# DT_AZP1524A1_SCH1_SHEET2__00A.net
KiCad netlist of a schematic drawn in Altium Designer
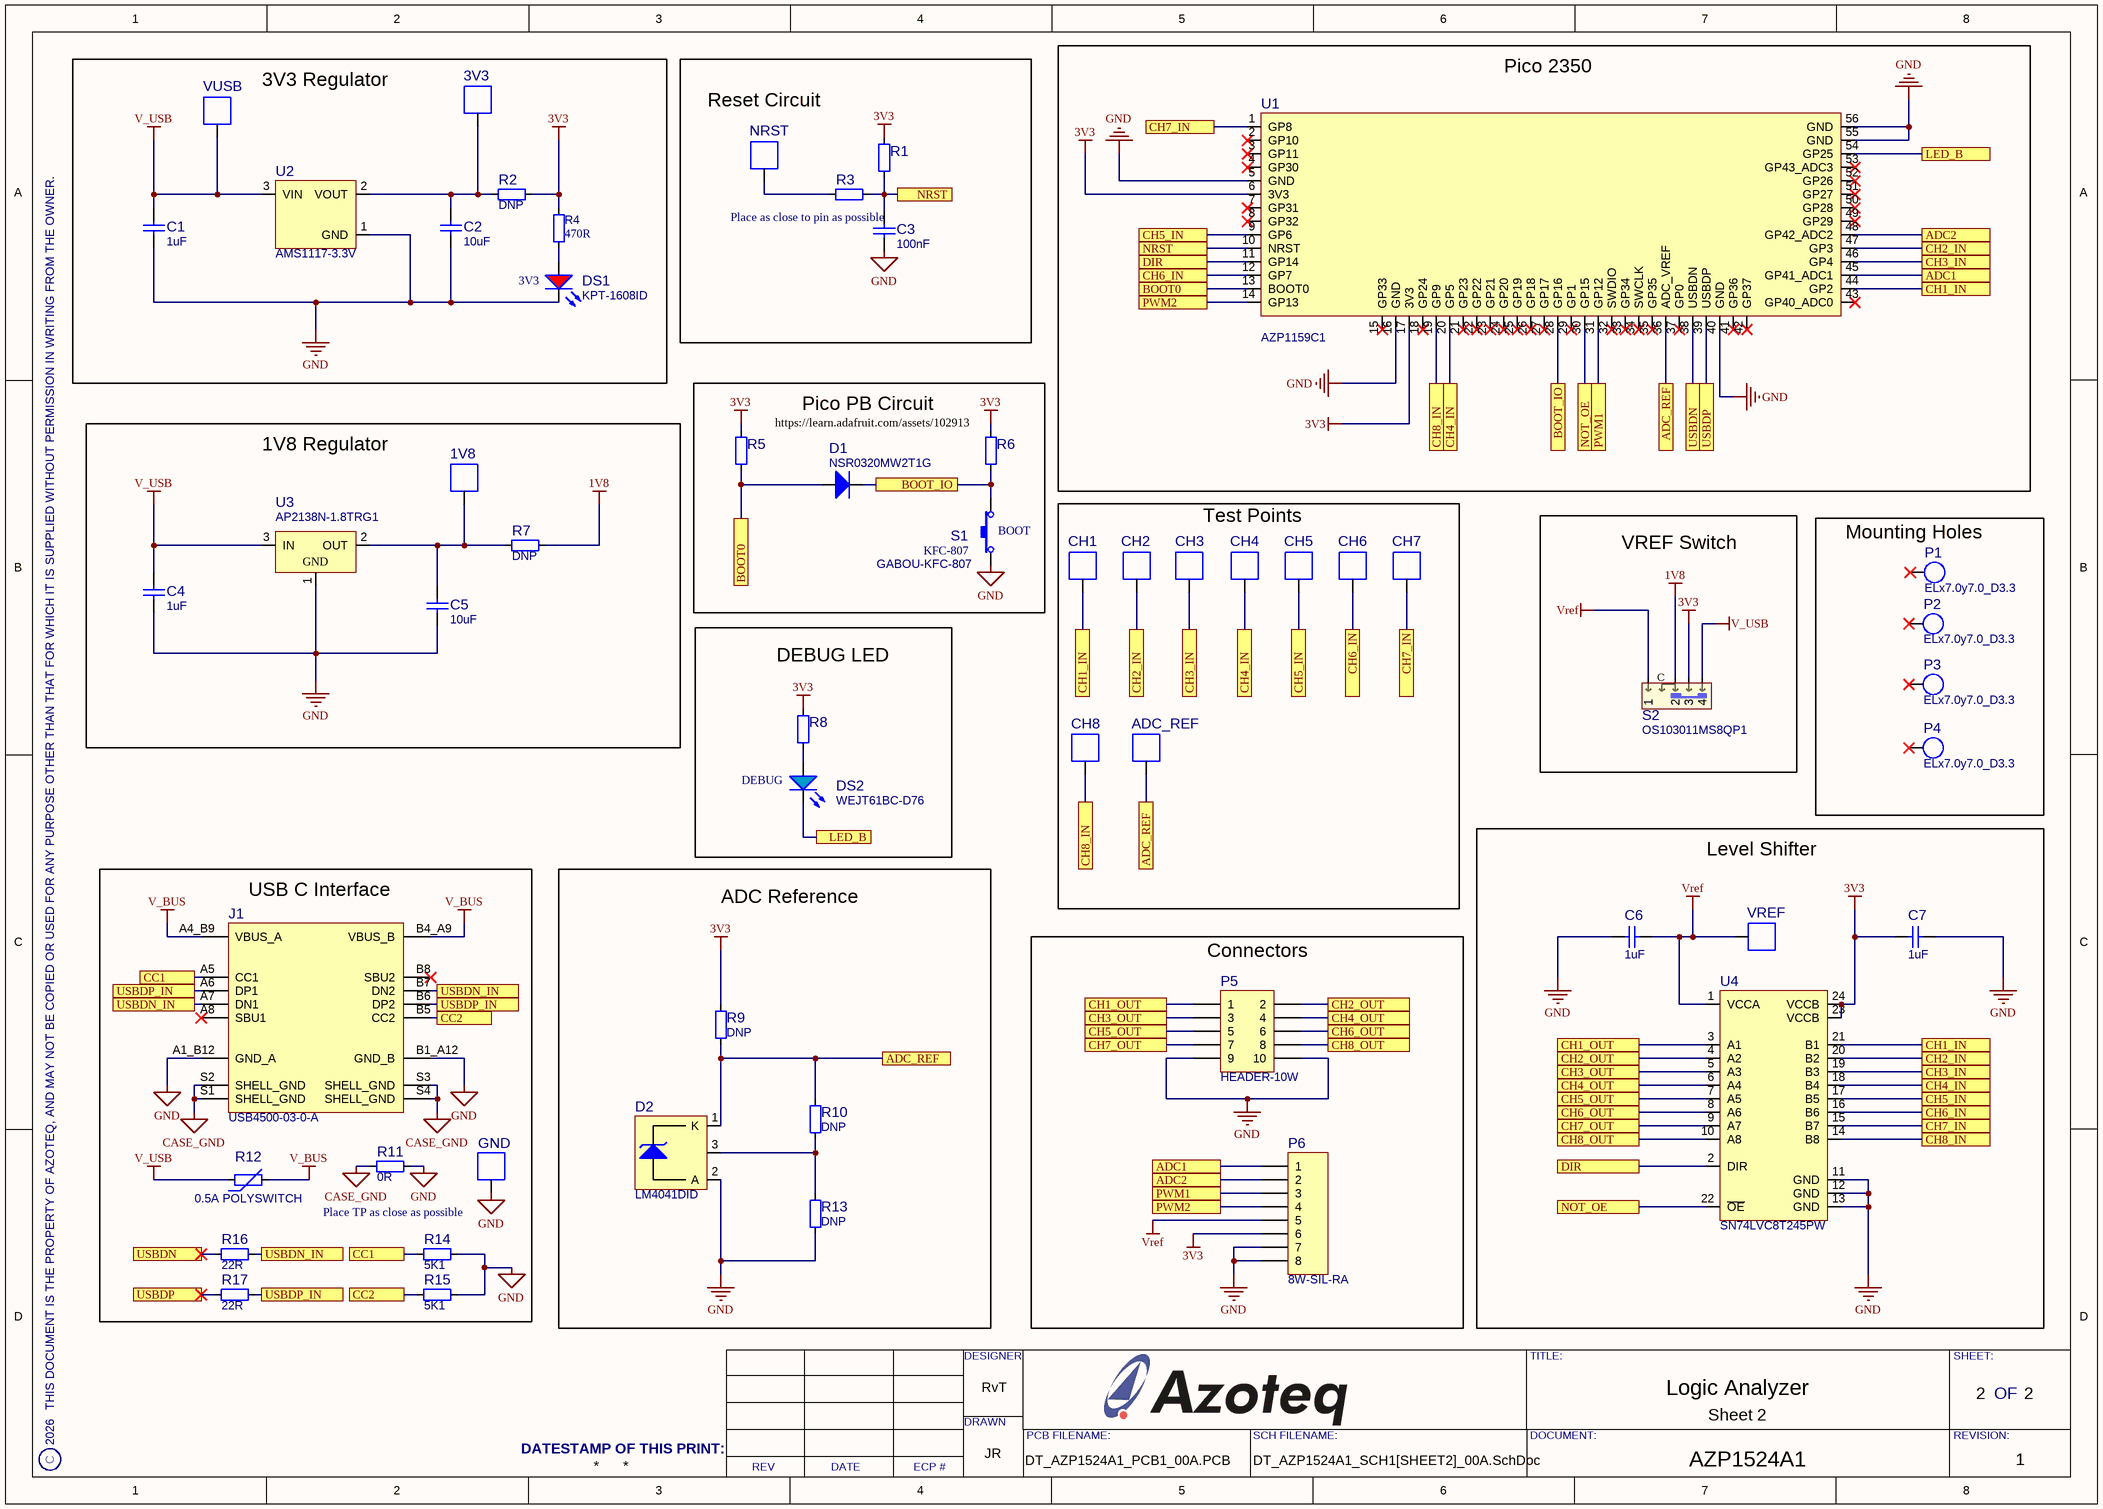
[diagram p0: DT_AZP1524A1_SCH1[SHEET2]_00A.SchDoc]

(export (version "E")
  (design (tool "Eeschema 10.0.6"))
  (components
    (comp (ref "1V8")
      (value "~")
      (footprint "TEST-POINT-1.5MM")
      (fields (field (name "CHECKED_BY") "*"))
      (libsource (lib "Miscellaneous") (part "TEST-POINT-SMD-1.5MM"))
    )
    (comp (ref "3V3")
      (value "~")
      (footprint "TEST-POINT-1.5MM")
      (fields (field (name "CHECKED_BY") "*"))
      (libsource (lib "Miscellaneous") (part "TEST-POINT-SMD-1.5MM"))
    )
    (comp (ref "ADC_REF")
      (value "~")
      (footprint "TEST-POINT-1.5MM")
      (fields (field (name "CHECKED_BY") "*"))
      (libsource (lib "Miscellaneous") (part "TEST-POINT-SMD-1.5MM"))
    )
    (comp (ref "C1")
      (value "1uF")
      (footprint "C-0603")
      (description "Capacitor, Ceramic, 1uF, 0603, X5R, 10%, 10V")
      (fields
        (field (name "INT_PART_NUMBER") "CAP0021")
        (field (name "MANUFACTURER") "Samsung")
        (field (name "CHECKED_BY") "Jason Reinecke")
      )
      (libsource (lib "Passive") (part "CAP 1u0F 0603 CER X5R 10% 10V"))
    )
    (comp (ref "C2")
      (value "10uF")
      (footprint "C-0603")
      (description "Capacitor, Ceramic, 10uF, 0603, X5R, 20%, 6V3 SAMSUNG")
      (fields
        (field (name "INT_PART_NUMBER") "CAP0076")
        (field (name "MANUFACTURER") "SAMSUNG")
        (field (name "CHECKED_BY") "Jason Reinecke")
      )
      (libsource (lib "Passive") (part "CAP 10uF 0603 CER X5R 20% 6V3 SAMSUNG"))
    )
    (comp (ref "C3")
      (value "100nF")
      (footprint "C-0603")
      (description "Capacitor, Ceramic, 100nF, 0603, X7R, 10%, 50V")
      (fields
        (field (name "INT_PART_NUMBER") "CAP0032")
        (field (name "MANUFACTURER") "Samsung")
        (field (name "CHECKED_BY") "Jason Reinecke")
      )
      (libsource (lib "Passive") (part "CAP 100nF 0603 CER X7R 10% 50V"))
    )
    (comp (ref "C4")
      (value "1uF")
      (footprint "C-0603")
      (description "Capacitor, Ceramic, 1uF, 0603, X5R, 10%, 10V")
      (fields
        (field (name "INT_PART_NUMBER") "CAP0021")
        (field (name "MANUFACTURER") "Samsung")
        (field (name "CHECKED_BY") "Jason Reinecke")
      )
      (libsource (lib "Passive") (part "CAP 1u0F 0603 CER X5R 10% 10V"))
    )
    (comp (ref "C5")
      (value "10uF")
      (footprint "C-0603")
      (description "Capacitor, Ceramic, 10uF, 0603, X5R, 20%, 6V3 SAMSUNG")
      (fields
        (field (name "INT_PART_NUMBER") "CAP0076")
        (field (name "MANUFACTURER") "SAMSUNG")
        (field (name "CHECKED_BY") "Jason Reinecke")
      )
      (libsource (lib "Passive") (part "CAP 10uF 0603 CER X5R 20% 6V3 SAMSUNG"))
    )
    (comp (ref "C6")
      (value "1uF")
      (footprint "C-0603")
      (description "Capacitor, Ceramic, 1uF, 0603, X5R, 10%, 10V")
      (fields
        (field (name "INT_PART_NUMBER") "CAP0021")
        (field (name "MANUFACTURER") "Samsung")
        (field (name "CHECKED_BY") "Jason Reinecke")
      )
      (libsource (lib "Passive") (part "CAP 1u0F 0603 CER X5R 10% 10V"))
    )
    (comp (ref "C7")
      (value "1uF")
      (footprint "C-0603")
      (description "Capacitor, Ceramic, 1uF, 0603, X5R, 10%, 10V")
      (fields
        (field (name "INT_PART_NUMBER") "CAP0021")
        (field (name "MANUFACTURER") "Samsung")
        (field (name "CHECKED_BY") "Jason Reinecke")
      )
      (libsource (lib "Passive") (part "CAP 1u0F 0603 CER X5R 10% 10V"))
    )
    (comp (ref "CH1")
      (value "~")
      (footprint "TEST-POINT-1.5MM")
      (fields (field (name "CHECKED_BY") "*"))
      (libsource (lib "Miscellaneous") (part "TEST-POINT-SMD-1.5MM"))
    )
    (comp (ref "CH2")
      (value "~")
      (footprint "TEST-POINT-1.5MM")
      (fields (field (name "CHECKED_BY") "*"))
      (libsource (lib "Miscellaneous") (part "TEST-POINT-SMD-1.5MM"))
    )
    (comp (ref "CH3")
      (value "~")
      (footprint "TEST-POINT-1.5MM")
      (fields (field (name "CHECKED_BY") "*"))
      (libsource (lib "Miscellaneous") (part "TEST-POINT-SMD-1.5MM"))
    )
    (comp (ref "CH4")
      (value "~")
      (footprint "TEST-POINT-1.5MM")
      (fields (field (name "CHECKED_BY") "*"))
      (libsource (lib "Miscellaneous") (part "TEST-POINT-SMD-1.5MM"))
    )
    (comp (ref "CH5")
      (value "~")
      (footprint "TEST-POINT-1.5MM")
      (fields (field (name "CHECKED_BY") "*"))
      (libsource (lib "Miscellaneous") (part "TEST-POINT-SMD-1.5MM"))
    )
    (comp (ref "CH6")
      (value "~")
      (footprint "TEST-POINT-1.5MM")
      (fields (field (name "CHECKED_BY") "*"))
      (libsource (lib "Miscellaneous") (part "TEST-POINT-SMD-1.5MM"))
    )
    (comp (ref "CH7")
      (value "~")
      (footprint "TEST-POINT-1.5MM")
      (fields (field (name "CHECKED_BY") "*"))
      (libsource (lib "Miscellaneous") (part "TEST-POINT-SMD-1.5MM"))
    )
    (comp (ref "CH8")
      (value "~")
      (footprint "TEST-POINT-1.5MM")
      (fields (field (name "CHECKED_BY") "*"))
      (libsource (lib "Miscellaneous") (part "TEST-POINT-SMD-1.5MM"))
    )
    (comp (ref "D1")
      (value "NSR0320MW2T1G")
      (footprint "D-SOD-323")
      (description "Diode Schottky 20V 1A 2-Pin SOD-323 T/R")
      (fields
        (field (name "INT_PART_NUMBER") "DIO0074")
        (field (name "MANUFACTURER") "ONsemiconductors")
        (field (name "CHECKED_BY") "*")
      )
      (libsource (lib "Discrete") (part "Diode Schottky 20V 1A SOD-323"))
    )
    (comp (ref "D2")
      (value "LM4041DID")
      (footprint "SOT-23")
      (fields (field (name "MANUFACTURER") "Texas Instruments") (field (name "CHECKED_BY") "*"))
      (libsource (lib "Discrete") (part "DIODE-ZENER-LM4041-SOT-23"))
    )
    (comp (ref "DS1")
      (value "KPT-1608ID")
      (footprint "D-LED-RED-0603")
      (fields (field (name "MANUFACTURER") "KingBright") (field (name "CHECKED_BY") "*"))
      (libsource (lib "Discrete") (part "LED-KPT1608ID-RED-0603"))
    )
    (comp (ref "DS2")
      (value "WEJT61BC-D76")
      (footprint "D-LED-BLUE-0603 - WEJ updated")
      (description "LED, WEJT61BC-D76, Blue, Vf=3.2V , If=30mA")
      (fields
        (field (name "INT_PART_NUMBER") "LED0098")
        (field (name "MANUFACTURER") "WEJ")
        (field (name "CHECKED_BY") "*")
      )
      (libsource (lib "Discrete") (part "LED-WEJT61BC-D76-BLUE-0603"))
    )
    (comp (ref "GND")
      (value "~")
      (footprint "TEST-POINT-1.5MM")
      (fields (field (name "CHECKED_BY") "*"))
      (libsource (lib "Miscellaneous") (part "TEST-POINT-SMD-1.5MM"))
    )
    (comp (ref "J1")
      (value "USB4500-03-0-A")
      (footprint "J-USB-GCT-USB4500-03-0-A")
      (description "USB-C TYPE REC 16P, 3U\" MID MNT 0.8MM USB2.0")
      (fields
        (field (name "INT_PART_NUMBER") "NONE")
        (field (name "MANUFACTURER") "GCT")
        (field (name "CHECKED_BY") "Jason Reinecke")
      )
      (libsource (lib "Connectors") (part "USB-GCT-USB4500-03-0-A"))
    )
    (comp (ref "NRST")
      (value "~")
      (footprint "TEST-POINT-1.5MM")
      (fields (field (name "CHECKED_BY") "*"))
      (libsource (lib "Miscellaneous") (part "TEST-POINT-SMD-1.5MM"))
    )
    (comp (ref "P1")
      (value "ELx7.0y7.0_D3.3")
      (footprint "MPAD-X7.0Y7.0_D3.3")
      (fields (field (name "CHECKED_BY") "*"))
      (libsource (lib "MPads") (part "MPAD-ELx7.0y7.0_D3.3"))
    )
    (comp (ref "P2")
      (value "ELx7.0y7.0_D3.3")
      (footprint "MPAD-X7.0Y7.0_D3.3")
      (fields (field (name "CHECKED_BY") "*"))
      (libsource (lib "MPads") (part "MPAD-ELx7.0y7.0_D3.3"))
    )
    (comp (ref "P3")
      (value "ELx7.0y7.0_D3.3")
      (footprint "MPAD-X7.0Y7.0_D3.3")
      (fields (field (name "CHECKED_BY") "*"))
      (libsource (lib "MPads") (part "MPAD-ELx7.0y7.0_D3.3"))
    )
    (comp (ref "P4")
      (value "ELx7.0y7.0_D3.3")
      (footprint "MPAD-X7.0Y7.0_D3.3")
      (fields (field (name "CHECKED_BY") "*"))
      (libsource (lib "MPads") (part "MPAD-ELx7.0y7.0_D3.3"))
    )
    (comp (ref "P5")
      (value "HEADER-10W")
      (footprint "P-BERG-10W-HDR-EDGE")
      (description "Connector, Header, Edge Mount,DIL, 10W, SMT")
      (fields (field (name "CHECKED_BY") "*"))
      (libsource (lib "Connectors") (part "BERG-10W-HDR-EDGE"))
    )
    (comp (ref "P6")
      (value "8W-SIL-RA")
      (footprint "P-BERG-8W-HDR-RA-SIL")
      (description "Connector, Header, Right angle, SIL, 8W, THP")
      (fields (field (name "MANUFACTURER") "Ho Chien"))
      (libsource (lib "Connectors") (part "BERG-8W-HDR-RA-SIL"))
    )
    (comp (ref "R1")
      (value "~")
      (footprint "R-0603")
      (description "Resistor, 0603, 5%, 0.1W")
      (fields
        (field (name "INT_PART_NUMBER") "MNFR04")
        (field (name "TOLERANCE") "5%")
        (field (name "CHECKED_BY") "Jason Reinecke")
      )
      (libsource (lib "Passive") (part "MNFR 0603 5% 0.1W"))
    )
    (comp (ref "R2")
      (value "DNP")
      (footprint "R-0603")
      (description "Resistor, DNP, 0603")
      (fields (field (name "CHECKED_BY") "Jason Reinecke"))
      (libsource (lib "Passive") (part "RES DNP 0603"))
    )
    (comp (ref "R3")
      (value "~")
      (footprint "R-0603")
      (description "Resistor, 0603, 5%, 0.1W")
      (fields
        (field (name "INT_PART_NUMBER") "MNFR04")
        (field (name "TOLERANCE") "5%")
        (field (name "CHECKED_BY") "Jason Reinecke")
      )
      (libsource (lib "") (part "MNFR 0603 5% 0.1W_1"))
    )
    (comp (ref "R4")
      (value "470R")
      (footprint "R-0603")
      (description "Res Thick Film 0603 470 Ohm 5% 0.1W(1/10W) ±100ppm/°C Molded SMD Paper T/R")
      (fields
        (field (name "INT_PART_NUMBER") "RES0307")
        (field (name "MANUFACTURER") "Yageo")
        (field (name "CHECKED_BY") "Jason Reinecke")
      )
      (libsource (lib "Passive") (part "RES 470R 0603 5% 0.1W Yageo"))
    )
    (comp (ref "R5")
      (value "~")
      (footprint "R-0603")
      (description "Resistor, 0603, 5%, 0.1W")
      (fields
        (field (name "INT_PART_NUMBER") "MNFR04")
        (field (name "TOLERANCE") "5%")
        (field (name "CHECKED_BY") "Jason Reinecke")
      )
      (libsource (lib "") (part "MNFR 0603 5% 0.1W_2"))
    )
    (comp (ref "R6")
      (value "~")
      (footprint "R-0603")
      (description "Resistor, 0603, 5%, 0.1W")
      (fields
        (field (name "INT_PART_NUMBER") "MNFR04")
        (field (name "TOLERANCE") "5%")
        (field (name "CHECKED_BY") "Jason Reinecke")
      )
      (libsource (lib "") (part "MNFR 0603 5% 0.1W_2"))
    )
    (comp (ref "R7")
      (value "DNP")
      (footprint "R-0603")
      (description "Resistor, DNP, 0603")
      (fields (field (name "CHECKED_BY") "Jason Reinecke"))
      (libsource (lib "Passive") (part "RES DNP 0603"))
    )
    (comp (ref "R8")
      (value "~")
      (footprint "R-0603")
      (description "Resistor, 0603, 5%, 0.1W")
      (fields
        (field (name "INT_PART_NUMBER") "MNFR04")
        (field (name "TOLERANCE") "5%")
        (field (name "CHECKED_BY") "Jason Reinecke")
      )
      (libsource (lib "Passive") (part "MNFR 0603 5% 0.1W"))
    )
    (comp (ref "R9")
      (value "DNP")
      (footprint "R-0603")
      (description "Resistor, DNP, 0603")
      (fields (field (name "CHECKED_BY") "Jason Reinecke"))
      (libsource (lib "") (part "RES DNP 0603_1"))
    )
    (comp (ref "R10")
      (value "DNP")
      (footprint "R-0603")
      (description "Resistor, DNP, 0603")
      (fields (field (name "CHECKED_BY") "Jason Reinecke"))
      (libsource (lib "") (part "RES DNP 0603_1"))
    )
    (comp (ref "R11")
      (value "0R")
      (footprint "R-0603")
      (description "Res Thick Film 0603 0 Ohm Molded SMD Paper T/R")
      (fields
        (field (name "INT_PART_NUMBER") "RES0139")
        (field (name "MANUFACTURER") "Yageo")
        (field (name "CHECKED_BY") "Jason Reinecke")
      )
      (libsource (lib "Passive") (part "RES 0R 0603 1% 0.1W Yageo"))
    )
    (comp (ref "R12")
      (value "0.5A POLYSWITCH")
      (footprint "R-POLYSWITCH-1206")
      (description "Polyswitch, nanoSMDC050F, 1206, 0.5A, 13.2V")
      (fields
        (field (name "INT_PART_NUMBER") "SWT0070")
        (field (name "MANUFACTURER") "Tyco")
        (field (name "CHECKED_BY") "Jason Reinecke")
      )
      (libsource (lib "Passive") (part "POLYSWITCH-nanoSMDC050F/13.2"))
    )
    (comp (ref "R13")
      (value "DNP")
      (footprint "R-0603")
      (description "Resistor, DNP, 0603")
      (fields (field (name "CHECKED_BY") "Jason Reinecke"))
      (libsource (lib "") (part "RES DNP 0603_1"))
    )
    (comp (ref "R14")
      (value "5K1")
      (footprint "R-0603")
      (description "Resistor, 0603, 1%, 0.1W")
      (fields
        (field (name "INT_PART_NUMBER") "MNFR03")
        (field (name "TOLERANCE") "1%")
        (field (name "CHECKED_BY") "*")
      )
      (libsource (lib "Passive") (part "MNFR 0603 1% 0.1W"))
    )
    (comp (ref "R15")
      (value "5K1")
      (footprint "R-0603")
      (description "Resistor, 0603, 1%, 0.1W")
      (fields
        (field (name "INT_PART_NUMBER") "MNFR03")
        (field (name "TOLERANCE") "1%")
        (field (name "CHECKED_BY") "*")
      )
      (libsource (lib "Passive") (part "MNFR 0603 1% 0.1W"))
    )
    (comp (ref "R16")
      (value "22R")
      (footprint "R-0603")
      (description "Resistor, 0603, 1%, 0.1W")
      (fields
        (field (name "INT_PART_NUMBER") "MNFR03")
        (field (name "TOLERANCE") "1%")
        (field (name "CHECKED_BY") "*")
      )
      (libsource (lib "Passive") (part "MNFR 0603 1% 0.1W"))
    )
    (comp (ref "R17")
      (value "22R")
      (footprint "R-0603")
      (description "Resistor, 0603, 1%, 0.1W")
      (fields
        (field (name "INT_PART_NUMBER") "MNFR03")
        (field (name "TOLERANCE") "1%")
        (field (name "CHECKED_BY") "*")
      )
      (libsource (lib "") (part "MNFR 0603 1% 0.1W_1"))
    )
    (comp (ref "S1")
      (value "GABOU-KFC-807")
      (footprint "S-GABOU-KFC-807")
      (description "SWITCH TACTILE SPST-NO 0.05A 12V")
      (fields
        (field (name "MANUFACTURER") "GABOU")
        (field (name "VOLTAGE") "12V")
        (field (name "ALTIUM_VALUE") "KFC-807")
      )
      (libsource (lib "Switches") (part "GABOU-KFC-807"))
    )
    (comp (ref "S2")
      (value "OS103011MS8QP1")
      (footprint "S-C&K-OS103011MS8QP1")
      (description "SWITCH SLIDE SP3T 100MA 12V")
      (fields (field (name "MANUFACTURER") "C&K") (field (name "3D_PART") "No"))
      (libsource (lib "Switches") (part "C&K-OS103011MS8QP1"))
    )
    (comp (ref "U1")
      (value "AZP1159C1")
      (footprint "AZP1159C1")
      (description "AZP115C01: RP2350 Stamp (Pi Pico) - stamp breakout")
      (fields
        (field (name "INT_PART_NUMBER") "NONE")
        (field (name "MANUFACTURER") "Azoteq")
        (field (name "CHECKED_BY") "Jason Reinecke")
      )
      (libsource (lib "Hardware") (part "AZP1159C1"))
    )
    (comp (ref "U2")
      (value "AMS1117-3.3V")
      (footprint "SOT-223")
      (description "IC, Voltage Regulator, 3.3V Out, 4.7-18V In, 1A")
      (fields
        (field (name "INT_PART_NUMBER") "NONE")
        (field (name "MANUFACTURER") "MSKSEMI")
        (field (name "CHECKED_BY") "Jason Reinecke")
      )
      (libsource (lib "IC") (part "AMS1117-MSKSEMI-SOT-223"))
    )
    (comp (ref "U3")
      (value "AP2138N-1.8TRG1")
      (footprint "SOT-23")
      (description "IC REG LINEAR 1.8V 250MA SOT23-3")
      (fields
        (field (name "MANUFACTURER") "Diodes Incorporated")
        (field (name "VOLTAGE") "1.8V")
        (field (name "CHECKED_BY") "Jason Reinecke")
      )
      (libsource (lib "IC") (part "AP2138N-1.8TRG1-SOT-23"))
    )
    (comp (ref "U4")
      (value "SN74LVC8T245PW")
      (footprint "U-TSSOP-24")
      (fields (field (name "MANUFACTURER") "Texas Instruments") (field (name "CHECKED_BY") "*"))
      (libsource (lib "IC") (part "SN74LVC8T245PW-TSSOP-24"))
    )
    (comp (ref "VREF")
      (value "~")
      (footprint "TEST-POINT-1.5MM")
      (fields (field (name "CHECKED_BY") "*"))
      (libsource (lib "Miscellaneous") (part "TEST-POINT-SMD-1.5MM"))
    )
    (comp (ref "VUSB")
      (value "~")
      (footprint "TEST-POINT-1.5MM")
      (fields (field (name "CHECKED_BY") "*"))
      (libsource (lib "Miscellaneous") (part "TEST-POINT-SMD-1.5MM"))
    )
  )
  (nets
    (net (code "1") (name "/ADC1") (class "Default")
      (node (ref "P6") (pin "1") (pinfunction "1_1") (pintype "passive"))
      (node (ref "U1") (pin "45") (pinfunction "GP41_ADC1_45") (pintype "passive"))
    )
    (net (code "2") (name "/ADC2") (class "Default")
      (node (ref "P6") (pin "2") (pinfunction "2_2") (pintype "passive"))
      (node (ref "U1") (pin "48") (pinfunction "GP42_ADC2_48") (pintype "passive"))
    )
    (net (code "3") (name "/ADC_REF") (class "Default")
      (node (ref "ADC_REF") (pin "1") (pinfunction "1_1") (pintype "passive"))
      (node (ref "D2") (pin "1") (pinfunction "K_1") (pintype "passive"))
      (node (ref "R10") (pin "2") (pinfunction "2_2") (pintype "passive"))
      (node (ref "R9") (pin "1") (pinfunction "1_1") (pintype "passive"))
      (node (ref "U1") (pin "36") (pinfunction "ADC_VREF_36") (pintype "passive"))
    )
    (net (code "4") (name "/BOOT0") (class "Default")
      (node (ref "D1") (pin "2") (pinfunction "K_2") (pintype "passive"))
      (node (ref "R5") (pin "2") (pinfunction "2_2") (pintype "passive"))
      (node (ref "U1") (pin "13") (pinfunction "BOOT0_13") (pintype "passive"))
    )
    (net (code "5") (name "/BOOT_IO") (class "Default")
      (node (ref "D1") (pin "1") (pinfunction "K_1") (pintype "passive"))
      (node (ref "R6") (pin "2") (pinfunction "2_2") (pintype "passive"))
      (node (ref "S1") (pin "2") (pinfunction "2_2") (pintype "passive"))
      (node (ref "U1") (pin "28") (pinfunction "GP16_28") (pintype "passive"))
    )
    (net (code "6") (name "/CC1") (class "Default")
      (node (ref "J1") (pin "A5") (pinfunction "CC1_A5") (pintype "passive"))
      (node (ref "R14") (pin "1") (pinfunction "1_1") (pintype "passive"))
    )
    (net (code "7") (name "/CC2") (class "Default")
      (node (ref "J1") (pin "B5") (pinfunction "CC2_B5") (pintype "passive"))
      (node (ref "R15") (pin "1") (pinfunction "1_1") (pintype "passive"))
    )
    (net (code "8") (name "/CH1_IN") (class "Default")
      (node (ref "CH1") (pin "1") (pinfunction "1_1") (pintype "passive"))
      (node (ref "U1") (pin "44") (pinfunction "GP2_44") (pintype "passive"))
      (node (ref "U4") (pin "21") (pinfunction "B1_21") (pintype "passive"))
    )
    (net (code "9") (name "/CH1_OUT") (class "Default")
      (node (ref "P5") (pin "1") (pinfunction "1_1") (pintype "passive"))
      (node (ref "U4") (pin "3") (pinfunction "A1_3") (pintype "passive"))
    )
    (net (code "10") (name "/CH2_IN") (class "Default")
      (node (ref "CH2") (pin "1") (pinfunction "1_1") (pintype "passive"))
      (node (ref "U1") (pin "47") (pinfunction "GP3_47") (pintype "passive"))
      (node (ref "U4") (pin "20") (pinfunction "B2_20") (pintype "passive"))
    )
    (net (code "11") (name "/CH2_OUT") (class "Default")
      (node (ref "P5") (pin "2") (pinfunction "2_2") (pintype "passive"))
      (node (ref "U4") (pin "4") (pinfunction "A2_4") (pintype "passive"))
    )
    (net (code "12") (name "/CH3_IN") (class "Default")
      (node (ref "CH3") (pin "1") (pinfunction "1_1") (pintype "passive"))
      (node (ref "U1") (pin "46") (pinfunction "GP4_46") (pintype "passive"))
      (node (ref "U4") (pin "19") (pinfunction "B3_19") (pintype "passive"))
    )
    (net (code "13") (name "/CH3_OUT") (class "Default")
      (node (ref "P5") (pin "3") (pinfunction "3_3") (pintype "passive"))
      (node (ref "U4") (pin "5") (pinfunction "A3_5") (pintype "passive"))
    )
    (net (code "14") (name "/CH4_IN") (class "Default")
      (node (ref "CH4") (pin "1") (pinfunction "1_1") (pintype "passive"))
      (node (ref "U1") (pin "20") (pinfunction "GP5_20") (pintype "passive"))
      (node (ref "U4") (pin "18") (pinfunction "B4_18") (pintype "passive"))
    )
    (net (code "15") (name "/CH4_OUT") (class "Default")
      (node (ref "P5") (pin "4") (pinfunction "4_4") (pintype "passive"))
      (node (ref "U4") (pin "6") (pinfunction "A4_6") (pintype "passive"))
    )
    (net (code "16") (name "/CH5_IN") (class "Default")
      (node (ref "CH5") (pin "1") (pinfunction "1_1") (pintype "passive"))
      (node (ref "U1") (pin "9") (pinfunction "GP6_9") (pintype "passive"))
      (node (ref "U4") (pin "17") (pinfunction "B5_17") (pintype "passive"))
    )
    (net (code "17") (name "/CH5_OUT") (class "Default")
      (node (ref "P5") (pin "5") (pinfunction "5_5") (pintype "passive"))
      (node (ref "U4") (pin "7") (pinfunction "A5_7") (pintype "passive"))
    )
    (net (code "18") (name "/CH6_IN") (class "Default")
      (node (ref "CH6") (pin "1") (pinfunction "1_1") (pintype "passive"))
      (node (ref "U1") (pin "12") (pinfunction "GP7_12") (pintype "passive"))
      (node (ref "U4") (pin "16") (pinfunction "B6_16") (pintype "passive"))
    )
    (net (code "19") (name "/CH6_OUT") (class "Default")
      (node (ref "P5") (pin "6") (pinfunction "6_6") (pintype "passive"))
      (node (ref "U4") (pin "8") (pinfunction "A6_8") (pintype "passive"))
    )
    (net (code "20") (name "/CH7_IN") (class "Default")
      (node (ref "CH7") (pin "1") (pinfunction "1_1") (pintype "passive"))
      (node (ref "U1") (pin "1") (pinfunction "GP8_1") (pintype "passive"))
      (node (ref "U4") (pin "15") (pinfunction "B7_15") (pintype "passive"))
    )
    (net (code "21") (name "/CH7_OUT") (class "Default")
      (node (ref "P5") (pin "7") (pinfunction "7_7") (pintype "passive"))
      (node (ref "U4") (pin "9") (pinfunction "A7_9") (pintype "passive"))
    )
    (net (code "22") (name "/CH8_IN") (class "Default")
      (node (ref "CH8") (pin "1") (pinfunction "1_1") (pintype "passive"))
      (node (ref "U1") (pin "19") (pinfunction "GP9_19") (pintype "passive"))
      (node (ref "U4") (pin "14") (pinfunction "B8_14") (pintype "passive"))
    )
    (net (code "23") (name "/CH8_OUT") (class "Default")
      (node (ref "P5") (pin "8") (pinfunction "8_8") (pintype "passive"))
      (node (ref "U4") (pin "10") (pinfunction "A8_10") (pintype "passive"))
    )
    (net (code "24") (name "/DIR") (class "Default")
      (node (ref "U1") (pin "11") (pinfunction "GP14_11") (pintype "passive"))
      (node (ref "U4") (pin "2") (pinfunction "DIR_2") (pintype "passive"))
    )
    (net (code "25") (name "/LED_B") (class "Default")
      (node (ref "DS2") (pin "1") (pinfunction "K_1") (pintype "passive"))
      (node (ref "U1") (pin "54") (pinfunction "GP25_54") (pintype "passive"))
    )
    (net (code "26") (name "/NOT_OE") (class "Default")
      (node (ref "U1") (pin "30") (pinfunction "GP15_30") (pintype "passive"))
      (node (ref "U4") (pin "22") (pinfunction "~{OE}_22") (pintype "passive"))
    )
    (net (code "27") (name "/NRST") (class "Default")
      (node (ref "C3") (pin "2") (pinfunction "2_2") (pintype "passive"))
      (node (ref "R1") (pin "1") (pinfunction "1_1") (pintype "passive"))
      (node (ref "R3") (pin "2") (pinfunction "2_2") (pintype "passive"))
      (node (ref "U1") (pin "10") (pinfunction "NRST_10") (pintype "passive"))
    )
    (net (code "28") (name "/PWM1") (class "Default")
      (node (ref "P6") (pin "3") (pinfunction "3_3") (pintype "passive"))
      (node (ref "U1") (pin "31") (pinfunction "GP12_31") (pintype "passive"))
    )
    (net (code "29") (name "/PWM2") (class "Default")
      (node (ref "P6") (pin "4") (pinfunction "4_4") (pintype "passive"))
      (node (ref "U1") (pin "14") (pinfunction "GP13_14") (pintype "passive"))
    )
    (net (code "30") (name "/USBDN") (class "Default")
      (node (ref "R16") (pin "1") (pinfunction "1_1") (pintype "passive"))
      (node (ref "U1") (pin "38") (pinfunction "USBDN_38") (pintype "passive"))
    )
    (net (code "31") (name "/USBDN_IN") (class "Default")
      (node (ref "J1") (pin "A7") (pinfunction "DN1_A7") (pintype "passive"))
      (node (ref "J1") (pin "B7") (pinfunction "DN2_B7") (pintype "passive"))
      (node (ref "R16") (pin "2") (pinfunction "2_2") (pintype "passive"))
    )
    (net (code "32") (name "/USBDP") (class "Default")
      (node (ref "R17") (pin "2") (pinfunction "2_2") (pintype "passive"))
      (node (ref "U1") (pin "39") (pinfunction "USBDP_39") (pintype "passive"))
    )
    (net (code "33") (name "/USBDP_IN") (class "Default")
      (node (ref "J1") (pin "A6") (pinfunction "DP1_A6") (pintype "passive"))
      (node (ref "J1") (pin "B6") (pinfunction "DP2_B6") (pintype "passive"))
      (node (ref "R17") (pin "1") (pinfunction "1_1") (pintype "passive"))
    )
    (net (code "34") (name "1V8") (class "Default")
      (node (ref "R7") (pin "2") (pinfunction "2_2") (pintype "passive"))
      (node (ref "S2") (pin "2") (pinfunction "2_2") (pintype "passive"))
    )
    (net (code "35") (name "3V3") (class "Default")
      (node (ref "C7") (pin "2") (pinfunction "2_2") (pintype "passive"))
      (node (ref "P6") (pin "6") (pinfunction "6_6") (pintype "passive"))
      (node (ref "R1") (pin "2") (pinfunction "2_2") (pintype "passive"))
      (node (ref "R2") (pin "2") (pinfunction "2_2") (pintype "passive"))
      (node (ref "R4") (pin "2") (pinfunction "2_2") (pintype "passive"))
      (node (ref "R5") (pin "1") (pinfunction "1_1") (pintype "passive"))
      (node (ref "R6") (pin "1") (pinfunction "1_1") (pintype "passive"))
      (node (ref "R8") (pin "2") (pinfunction "2_2") (pintype "passive"))
      (node (ref "R9") (pin "2") (pinfunction "2_2") (pintype "passive"))
      (node (ref "S2") (pin "3") (pinfunction "3_3") (pintype "passive"))
      (node (ref "U1") (pin "17") (pinfunction "3V3_17") (pintype "passive"))
      (node (ref "U1") (pin "6") (pinfunction "3V3_6") (pintype "passive"))
      (node (ref "U4") (pin "23") (pinfunction "VCCB_23") (pintype "passive"))
      (node (ref "U4") (pin "24") (pinfunction "VCCB_24") (pintype "passive"))
    )
    (net (code "36") (name "CASE_GND") (class "Default")
      (node (ref "J1") (pin "S1") (pinfunction "SHELL_GND_S1") (pintype "passive"))
      (node (ref "J1") (pin "S2") (pinfunction "SHELL_GND_S2") (pintype "passive"))
      (node (ref "J1") (pin "S3") (pinfunction "SHELL_GND_S3") (pintype "passive"))
      (node (ref "J1") (pin "S4") (pinfunction "SHELL_GND_S4") (pintype "passive"))
      (node (ref "R11") (pin "1") (pinfunction "1_1") (pintype "passive"))
    )
    (net (code "37") (name "GND") (class "Default")
      (node (ref "C1") (pin "1") (pinfunction "1_1") (pintype "passive"))
      (node (ref "C2") (pin "1") (pinfunction "1_1") (pintype "passive"))
      (node (ref "C3") (pin "1") (pinfunction "1_1") (pintype "passive"))
      (node (ref "C4") (pin "1") (pinfunction "1_1") (pintype "passive"))
      (node (ref "C5") (pin "1") (pinfunction "1_1") (pintype "passive"))
      (node (ref "C6") (pin "2") (pinfunction "2_2") (pintype "passive"))
      (node (ref "C7") (pin "1") (pinfunction "1_1") (pintype "passive"))
      (node (ref "D2") (pin "2") (pinfunction "A_2") (pintype "passive"))
      (node (ref "DS1") (pin "1") (pinfunction "K_1") (pintype "passive"))
      (node (ref "GND") (pin "1") (pinfunction "1_1") (pintype "passive"))
      (node (ref "J1") (pin "A1_B12") (pinfunction "GND_A_A1_B12") (pintype "passive"))
      (node (ref "J1") (pin "B1_A12") (pinfunction "GND_B_B1_A12") (pintype "passive"))
      (node (ref "P5") (pin "10") (pinfunction "10_10") (pintype "passive"))
      (node (ref "P5") (pin "9") (pinfunction "9_9") (pintype "passive"))
      (node (ref "P6") (pin "7") (pinfunction "7_7") (pintype "passive"))
      (node (ref "P6") (pin "8") (pinfunction "8_8") (pintype "passive"))
      (node (ref "R11") (pin "2") (pinfunction "2_2") (pintype "passive"))
      (node (ref "R13") (pin "1") (pinfunction "1_1") (pintype "passive"))
      (node (ref "R14") (pin "2") (pinfunction "2_2") (pintype "passive"))
      (node (ref "R15") (pin "2") (pinfunction "2_2") (pintype "passive"))
      (node (ref "S1") (pin "1") (pinfunction "1_1") (pintype "passive"))
      (node (ref "U1") (pin "16") (pinfunction "GND_16") (pintype "passive"))
      (node (ref "U1") (pin "40") (pinfunction "GND_40") (pintype "passive"))
      (node (ref "U1") (pin "5") (pinfunction "GND_5") (pintype "passive"))
      (node (ref "U1") (pin "55") (pinfunction "GND_55") (pintype "passive"))
      (node (ref "U1") (pin "56") (pinfunction "GND_56") (pintype "passive"))
      (node (ref "U2") (pin "1") (pinfunction "GND_1") (pintype "passive"))
      (node (ref "U3") (pin "1") (pinfunction "GND_1") (pintype "passive"))
      (node (ref "U4") (pin "11") (pinfunction "GND_11") (pintype "passive"))
      (node (ref "U4") (pin "12") (pinfunction "GND_12") (pintype "passive"))
      (node (ref "U4") (pin "13") (pinfunction "GND_13") (pintype "passive"))
    )
    (net (code "38") (name "Net-(D2-Pad3)") (class "Default")
      (node (ref "D2") (pin "3") (pintype "passive"))
      (node (ref "R10") (pin "1") (pinfunction "1_1") (pintype "passive"))
      (node (ref "R13") (pin "2") (pinfunction "2_2") (pintype "passive"))
    )
    (net (code "39") (name "Net-(DS1-A)") (class "Default")
      (node (ref "DS1") (pin "2") (pinfunction "A_2") (pintype "passive"))
      (node (ref "R4") (pin "1") (pinfunction "1_1") (pintype "passive"))
    )
    (net (code "40") (name "Net-(DS2-A)") (class "Default")
      (node (ref "DS2") (pin "2") (pinfunction "A_2") (pintype "passive"))
      (node (ref "R8") (pin "1") (pinfunction "1_1") (pintype "passive"))
    )
    (net (code "41") (name "Net-(NRST-Pad1)") (class "Default")
      (node (ref "NRST") (pin "1") (pinfunction "1_1") (pintype "passive"))
      (node (ref "R3") (pin "1") (pinfunction "1_1") (pintype "passive"))
    )
    (net (code "42") (name "Net-(U2-VOUT)") (class "Default")
      (node (ref "3V3") (pin "1") (pinfunction "1_1") (pintype "passive"))
      (node (ref "C2") (pin "2") (pinfunction "2_2") (pintype "passive"))
      (node (ref "R2") (pin "1") (pinfunction "1_1") (pintype "passive"))
      (node (ref "U2") (pin "2") (pinfunction "VOUT_2") (pintype "passive"))
    )
    (net (code "43") (name "Net-(U3-OUT)") (class "Default")
      (node (ref "1V8") (pin "1") (pinfunction "1_1") (pintype "passive"))
      (node (ref "C5") (pin "2") (pinfunction "2_2") (pintype "passive"))
      (node (ref "R7") (pin "1") (pinfunction "1_1") (pintype "passive"))
      (node (ref "U3") (pin "2") (pinfunction "OUT_2") (pintype "passive"))
    )
    (net (code "44") (name "V_BUS") (class "Default")
      (node (ref "J1") (pin "A4_B9") (pinfunction "VBUS_A_A4_B9") (pintype "passive"))
      (node (ref "J1") (pin "B4_A9") (pinfunction "VBUS_B_B4_A9") (pintype "passive"))
      (node (ref "R12") (pin "2") (pinfunction "2_2") (pintype "passive"))
    )
    (net (code "45") (name "V_USB") (class "Default")
      (node (ref "C1") (pin "2") (pinfunction "2_2") (pintype "passive"))
      (node (ref "C4") (pin "2") (pinfunction "2_2") (pintype "passive"))
      (node (ref "R12") (pin "1") (pinfunction "1_1") (pintype "passive"))
      (node (ref "S2") (pin "4") (pinfunction "4_4") (pintype "passive"))
      (node (ref "U2") (pin "3") (pinfunction "VIN_3") (pintype "passive"))
      (node (ref "U3") (pin "3") (pinfunction "IN_3") (pintype "passive"))
      (node (ref "VUSB") (pin "1") (pinfunction "1_1") (pintype "passive"))
    )
    (net (code "46") (name "Vref") (class "Default")
      (node (ref "C6") (pin "1") (pinfunction "1_1") (pintype "passive"))
      (node (ref "P6") (pin "5") (pinfunction "5_5") (pintype "passive"))
      (node (ref "S2") (pin "1") (pinfunction "1_1") (pintype "passive"))
      (node (ref "U4") (pin "1") (pinfunction "VCCA_1") (pintype "passive"))
      (node (ref "VREF") (pin "1") (pinfunction "1_1") (pintype "passive"))
    )
    (net (code "47") (name "unconnected-(J1-SBU1-PadA8)") (class "Default")
      (node (ref "J1") (pin "A8") (pinfunction "SBU1_A8") (pintype "passive+no_connect"))
    )
    (net (code "48") (name "unconnected-(J1-SBU2-PadB8)") (class "Default")
      (node (ref "J1") (pin "B8") (pinfunction "SBU2_B8") (pintype "passive+no_connect"))
    )
    (net (code "49") (name "unconnected-(P1-Pad1)") (class "Default")
      (node (ref "P1") (pin "1") (pintype "passive+no_connect"))
    )
    (net (code "50") (name "unconnected-(P2-Pad1)") (class "Default")
      (node (ref "P2") (pin "1") (pintype "passive+no_connect"))
    )
    (net (code "51") (name "unconnected-(P3-Pad1)") (class "Default")
      (node (ref "P3") (pin "1") (pintype "passive+no_connect"))
    )
    (net (code "52") (name "unconnected-(P4-Pad1)") (class "Default")
      (node (ref "P4") (pin "1") (pintype "passive+no_connect"))
    )
    (net (code "53") (name "unconnected-(U1-GP0-Pad37)") (class "Default")
      (node (ref "U1") (pin "37") (pinfunction "GP0_37") (pintype "passive+no_connect"))
    )
    (net (code "54") (name "unconnected-(U1-GP1-Pad29)") (class "Default")
      (node (ref "U1") (pin "29") (pinfunction "GP1_29") (pintype "passive+no_connect"))
    )
    (net (code "55") (name "unconnected-(U1-GP10-Pad2)") (class "Default")
      (node (ref "U1") (pin "2") (pinfunction "GP10_2") (pintype "passive+no_connect"))
    )
    (net (code "56") (name "unconnected-(U1-GP11-Pad3)") (class "Default")
      (node (ref "U1") (pin "3") (pinfunction "GP11_3") (pintype "passive+no_connect"))
    )
    (net (code "57") (name "unconnected-(U1-GP17-Pad27)") (class "Default")
      (node (ref "U1") (pin "27") (pinfunction "GP17_27") (pintype "passive+no_connect"))
    )
    (net (code "58") (name "unconnected-(U1-GP18-Pad26)") (class "Default")
      (node (ref "U1") (pin "26") (pinfunction "GP18_26") (pintype "passive+no_connect"))
    )
    (net (code "59") (name "unconnected-(U1-GP19-Pad25)") (class "Default")
      (node (ref "U1") (pin "25") (pinfunction "GP19_25") (pintype "passive+no_connect"))
    )
    (net (code "60") (name "unconnected-(U1-GP20-Pad24)") (class "Default")
      (node (ref "U1") (pin "24") (pinfunction "GP20_24") (pintype "passive+no_connect"))
    )
    (net (code "61") (name "unconnected-(U1-GP21-Pad23)") (class "Default")
      (node (ref "U1") (pin "23") (pinfunction "GP21_23") (pintype "passive+no_connect"))
    )
    (net (code "62") (name "unconnected-(U1-GP22-Pad22)") (class "Default")
      (node (ref "U1") (pin "22") (pinfunction "GP22_22") (pintype "passive+no_connect"))
    )
    (net (code "63") (name "unconnected-(U1-GP23-Pad21)") (class "Default")
      (node (ref "U1") (pin "21") (pinfunction "GP23_21") (pintype "passive+no_connect"))
    )
    (net (code "64") (name "unconnected-(U1-GP24-Pad18)") (class "Default")
      (node (ref "U1") (pin "18") (pinfunction "GP24_18") (pintype "passive+no_connect"))
    )
    (net (code "65") (name "unconnected-(U1-GP26-Pad52)") (class "Default")
      (node (ref "U1") (pin "52") (pinfunction "GP26_52") (pintype "passive+no_connect"))
    )
    (net (code "66") (name "unconnected-(U1-GP27-Pad51)") (class "Default")
      (node (ref "U1") (pin "51") (pinfunction "GP27_51") (pintype "passive+no_connect"))
    )
    (net (code "67") (name "unconnected-(U1-GP28-Pad50)") (class "Default")
      (node (ref "U1") (pin "50") (pinfunction "GP28_50") (pintype "passive+no_connect"))
    )
    (net (code "68") (name "unconnected-(U1-GP29-Pad49)") (class "Default")
      (node (ref "U1") (pin "49") (pinfunction "GP29_49") (pintype "passive+no_connect"))
    )
    (net (code "69") (name "unconnected-(U1-GP30-Pad4)") (class "Default")
      (node (ref "U1") (pin "4") (pinfunction "GP30_4") (pintype "passive+no_connect"))
    )
    (net (code "70") (name "unconnected-(U1-GP31-Pad7)") (class "Default")
      (node (ref "U1") (pin "7") (pinfunction "GP31_7") (pintype "passive+no_connect"))
    )
    (net (code "71") (name "unconnected-(U1-GP32-Pad8)") (class "Default")
      (node (ref "U1") (pin "8") (pinfunction "GP32_8") (pintype "passive+no_connect"))
    )
    (net (code "72") (name "unconnected-(U1-GP33-Pad15)") (class "Default")
      (node (ref "U1") (pin "15") (pinfunction "GP33_15") (pintype "passive+no_connect"))
    )
    (net (code "73") (name "unconnected-(U1-GP34-Pad33)") (class "Default")
      (node (ref "U1") (pin "33") (pinfunction "GP34_33") (pintype "passive+no_connect"))
    )
    (net (code "74") (name "unconnected-(U1-GP35-Pad35)") (class "Default")
      (node (ref "U1") (pin "35") (pinfunction "GP35_35") (pintype "passive+no_connect"))
    )
    (net (code "75") (name "unconnected-(U1-GP36-Pad41)") (class "Default")
      (node (ref "U1") (pin "41") (pinfunction "GP36_41") (pintype "passive+no_connect"))
    )
    (net (code "76") (name "unconnected-(U1-GP37-Pad42)") (class "Default")
      (node (ref "U1") (pin "42") (pinfunction "GP37_42") (pintype "passive+no_connect"))
    )
    (net (code "77") (name "unconnected-(U1-GP40_ADC0-Pad43)") (class "Default")
      (node (ref "U1") (pin "43") (pinfunction "GP40_ADC0_43") (pintype "passive+no_connect"))
    )
    (net (code "78") (name "unconnected-(U1-GP43_ADC3-Pad53)") (class "Default")
      (node (ref "U1") (pin "53") (pinfunction "GP43_ADC3_53") (pintype "passive+no_connect"))
    )
    (net (code "79") (name "unconnected-(U1-SWCLK-Pad34)") (class "Default")
      (node (ref "U1") (pin "34") (pinfunction "SWCLK_34") (pintype "passive+no_connect"))
    )
    (net (code "80") (name "unconnected-(U1-SWDIO-Pad32)") (class "Default")
      (node (ref "U1") (pin "32") (pinfunction "SWDIO_32") (pintype "passive+no_connect"))
    )
  )
)
